# Apex_CV_Expander_UI.net
KiCad netlist of a schematic drawn in EAGLE
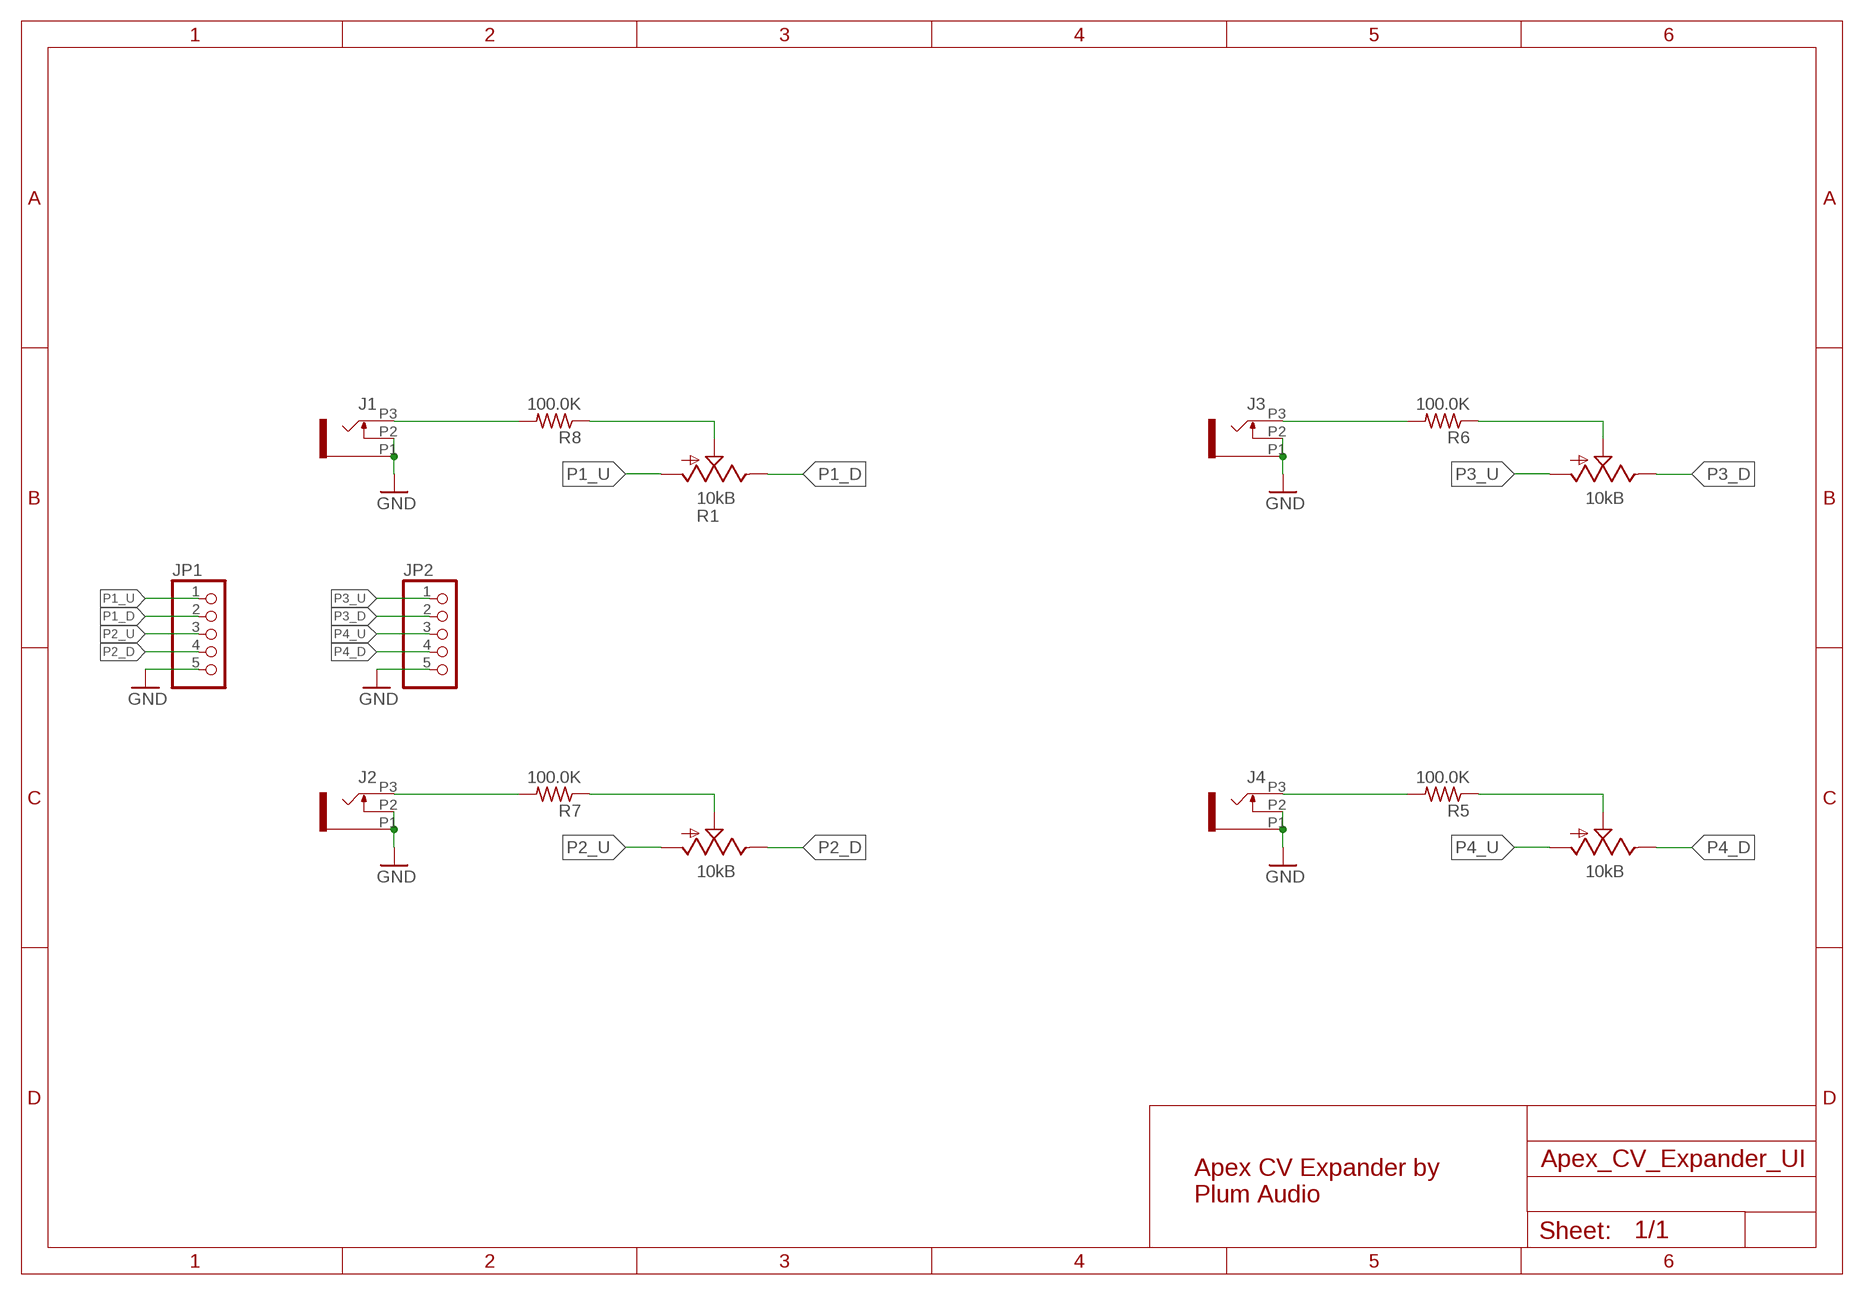
[diagram p0: schematic, sheet 1]

(export (version "E")
  (design (tool "Eeschema 10.0.6"))
  (components
    (comp (ref "J1")
      (value "OG-PJ301_PJ301_THONKICONN6")
      (footprint "eagle-import:OG-PJ301_WQP_PJ_301M6")
      (libsource (lib "eagle-import") (part "OG-PJ301_PJ301_THONKICONN6"))
    )
    (comp (ref "J2")
      (value "OG-PJ301_PJ301_THONKICONN6")
      (footprint "eagle-import:OG-PJ301_WQP_PJ_301M6")
      (libsource (lib "eagle-import") (part "OG-PJ301_PJ301_THONKICONN6"))
    )
    (comp (ref "J3")
      (value "OG-PJ301_PJ301_THONKICONN6")
      (footprint "eagle-import:OG-PJ301_WQP_PJ_301M6")
      (libsource (lib "eagle-import") (part "OG-PJ301_PJ301_THONKICONN6"))
    )
    (comp (ref "J4")
      (value "OG-PJ301_PJ301_THONKICONN6")
      (footprint "eagle-import:OG-PJ301_WQP_PJ_301M6")
      (libsource (lib "eagle-import") (part "OG-PJ301_PJ301_THONKICONN6"))
    )
    (comp (ref "JP1")
      (value "PINHD-1X5")
      (footprint "eagle-import:1X05")
      (libsource (lib "eagle-import") (part "PINHD-1X5"))
    )
    (comp (ref "JP2")
      (value "PINHD-1X5")
      (footprint "eagle-import:1X05")
      (libsource (lib "eagle-import") (part "PINHD-1X5"))
    )
    (comp (ref "R1")
      (value "10kB")
      (footprint "eagle-import:POTS_TALL_TRIMMER_POT_VERTICAL_SLOTED")
      (libsource (lib "eagle-import") (part "POTS_POT_USSLOTED_TALL_TRIMMER"))
    )
    (comp (ref "R2")
      (value "10kB")
      (footprint "eagle-import:POTS_TALL_TRIMMER_POT_VERTICAL_SLOTED")
      (libsource (lib "eagle-import") (part "POTS_POT_USSLOTED_TALL_TRIMMER"))
    )
    (comp (ref "R3")
      (value "10kB")
      (footprint "eagle-import:POTS_TALL_TRIMMER_POT_VERTICAL_SLOTED")
      (libsource (lib "eagle-import") (part "POTS_POT_USSLOTED_TALL_TRIMMER"))
    )
    (comp (ref "R4")
      (value "10kB")
      (footprint "eagle-import:POTS_TALL_TRIMMER_POT_VERTICAL_SLOTED")
      (libsource (lib "eagle-import") (part "POTS_POT_USSLOTED_TALL_TRIMMER"))
    )
    (comp (ref "R5")
      (value "100.0K")
      (footprint "eagle-import:R0603")
      (libsource (lib "eagle-import") (part "R-US_R0603"))
    )
    (comp (ref "R6")
      (value "100.0K")
      (footprint "eagle-import:R0603")
      (libsource (lib "eagle-import") (part "R-US_R0603"))
    )
    (comp (ref "R7")
      (value "100.0K")
      (footprint "eagle-import:R0603")
      (libsource (lib "eagle-import") (part "R-US_R0603"))
    )
    (comp (ref "R8")
      (value "100.0K")
      (footprint "eagle-import:R0603")
      (libsource (lib "eagle-import") (part "R-US_R0603"))
    )
  )
  (nets
    (net (code "1") (name "GND") (class "Default")
      (node (ref "J1") (pin "P1") (pinfunction "1_P1") (pintype "passive"))
      (node (ref "J1") (pin "P2") (pinfunction "2_P2") (pintype "passive"))
      (node (ref "J2") (pin "P1") (pinfunction "1_P1") (pintype "passive"))
      (node (ref "J2") (pin "P2") (pinfunction "2_P2") (pintype "passive"))
      (node (ref "J3") (pin "P1") (pinfunction "1_P1") (pintype "passive"))
      (node (ref "J3") (pin "P2") (pinfunction "2_P2") (pintype "passive"))
      (node (ref "J4") (pin "P1") (pinfunction "1_P1") (pintype "passive"))
      (node (ref "J4") (pin "P2") (pinfunction "2_P2") (pintype "passive"))
      (node (ref "JP1") (pin "5") (pinfunction "5_5") (pintype "passive"))
      (node (ref "JP2") (pin "5") (pinfunction "5_5") (pintype "passive"))
    )
    (net (code "2") (name "Net-(J1-3)") (class "Default")
      (node (ref "J1") (pin "P3") (pinfunction "3_P3") (pintype "passive"))
      (node (ref "R8") (pin "2") (pinfunction "2_2") (pintype "passive"))
    )
    (net (code "3") (name "Net-(J2-3)") (class "Default")
      (node (ref "J2") (pin "P3") (pinfunction "3_P3") (pintype "passive"))
      (node (ref "R7") (pin "2") (pinfunction "2_2") (pintype "passive"))
    )
    (net (code "4") (name "Net-(J3-3)") (class "Default")
      (node (ref "J3") (pin "P3") (pinfunction "3_P3") (pintype "passive"))
      (node (ref "R6") (pin "2") (pinfunction "2_2") (pintype "passive"))
    )
    (net (code "5") (name "Net-(J4-3)") (class "Default")
      (node (ref "J4") (pin "P3") (pinfunction "3_P3") (pintype "passive"))
      (node (ref "R5") (pin "2") (pinfunction "2_2") (pintype "passive"))
    )
    (net (code "6") (name "Net-(R1-S)") (class "Default")
      (node (ref "R1") (pin "P$2") (pinfunction "S_P$2") (pintype "passive"))
      (node (ref "R8") (pin "1") (pinfunction "1_1") (pintype "passive"))
    )
    (net (code "7") (name "Net-(R2-S)") (class "Default")
      (node (ref "R2") (pin "P$2") (pinfunction "S_P$2") (pintype "passive"))
      (node (ref "R7") (pin "1") (pinfunction "1_1") (pintype "passive"))
    )
    (net (code "8") (name "Net-(R3-S)") (class "Default")
      (node (ref "R3") (pin "P$2") (pinfunction "S_P$2") (pintype "passive"))
      (node (ref "R6") (pin "1") (pinfunction "1_1") (pintype "passive"))
    )
    (net (code "9") (name "Net-(R4-S)") (class "Default")
      (node (ref "R4") (pin "P$2") (pinfunction "S_P$2") (pintype "passive"))
      (node (ref "R5") (pin "1") (pinfunction "1_1") (pintype "passive"))
    )
    (net (code "10") (name "P1_D") (class "Default")
      (node (ref "JP1") (pin "2") (pinfunction "2_2") (pintype "passive"))
      (node (ref "R1") (pin "P$1") (pinfunction "E_P$1") (pintype "passive"))
    )
    (net (code "11") (name "P1_U") (class "Default")
      (node (ref "JP1") (pin "1") (pinfunction "1_1") (pintype "passive"))
      (node (ref "R1") (pin "P$3") (pinfunction "A_P$3") (pintype "passive"))
    )
    (net (code "12") (name "P2_D") (class "Default")
      (node (ref "JP1") (pin "4") (pinfunction "4_4") (pintype "passive"))
      (node (ref "R2") (pin "P$1") (pinfunction "E_P$1") (pintype "passive"))
    )
    (net (code "13") (name "P2_U") (class "Default")
      (node (ref "JP1") (pin "3") (pinfunction "3_3") (pintype "passive"))
      (node (ref "R2") (pin "P$3") (pinfunction "A_P$3") (pintype "passive"))
    )
    (net (code "14") (name "P3_D") (class "Default")
      (node (ref "JP2") (pin "2") (pinfunction "2_2") (pintype "passive"))
      (node (ref "R3") (pin "P$1") (pinfunction "E_P$1") (pintype "passive"))
    )
    (net (code "15") (name "P3_U") (class "Default")
      (node (ref "JP2") (pin "1") (pinfunction "1_1") (pintype "passive"))
      (node (ref "R3") (pin "P$3") (pinfunction "A_P$3") (pintype "passive"))
    )
    (net (code "16") (name "P4_D") (class "Default")
      (node (ref "JP2") (pin "4") (pinfunction "4_4") (pintype "passive"))
      (node (ref "R4") (pin "P$1") (pinfunction "E_P$1") (pintype "passive"))
    )
    (net (code "17") (name "P4_U") (class "Default")
      (node (ref "JP2") (pin "3") (pinfunction "3_3") (pintype "passive"))
      (node (ref "R4") (pin "P$3") (pinfunction "A_P$3") (pintype "passive"))
    )
  )
)
